# H4_MainController_Rev_1.net
KiCad netlist of a schematic drawn in EAGLE
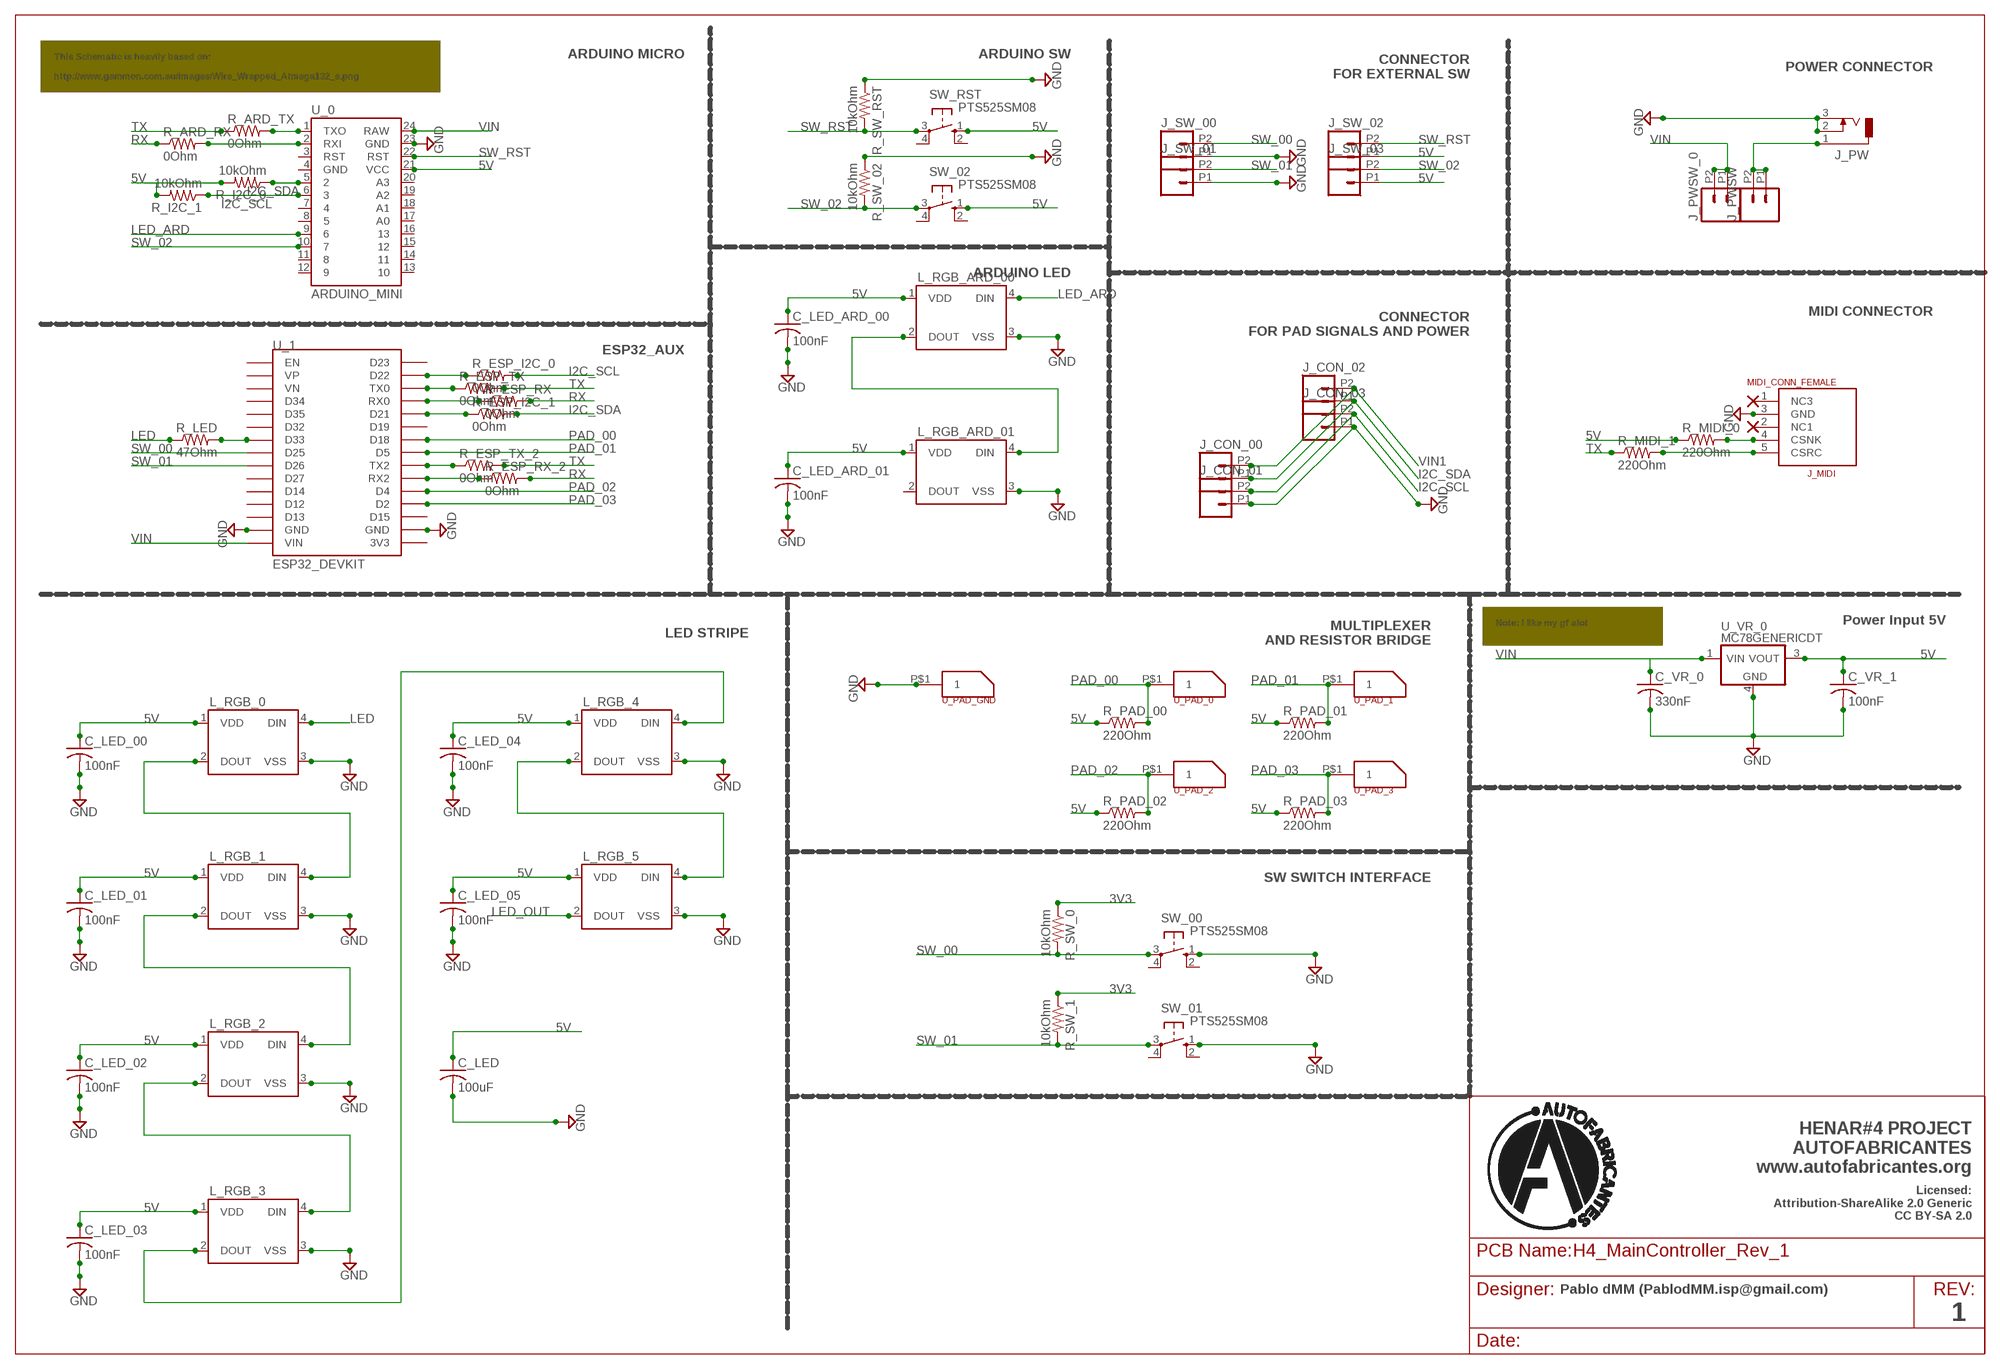
[diagram p0: schematic, sheet 1]

(export (version "E")
  (design (tool "Eeschema 10.0.6"))
  (components
    (comp (ref "C_LED")
      (value "100uF")
      (footprint "eagle-import:C1210")
      (libsource (lib "eagle-import") (part "C-USC1210"))
    )
    (comp (ref "C_LED_00")
      (value "100nF")
      (footprint "eagle-import:C0805K")
      (libsource (lib "eagle-import") (part "C-USC0805K"))
    )
    (comp (ref "C_LED_01")
      (value "100nF")
      (footprint "eagle-import:C0805K")
      (libsource (lib "eagle-import") (part "C-USC0805K"))
    )
    (comp (ref "C_LED_02")
      (value "100nF")
      (footprint "eagle-import:C0805K")
      (libsource (lib "eagle-import") (part "C-USC0805K"))
    )
    (comp (ref "C_LED_03")
      (value "100nF")
      (footprint "eagle-import:C0805K")
      (libsource (lib "eagle-import") (part "C-USC0805K"))
    )
    (comp (ref "C_LED_04")
      (value "100nF")
      (footprint "eagle-import:C0805K")
      (libsource (lib "eagle-import") (part "C-USC0805K"))
    )
    (comp (ref "C_LED_05")
      (value "100nF")
      (footprint "eagle-import:C0805K")
      (libsource (lib "eagle-import") (part "C-USC0805K"))
    )
    (comp (ref "C_LED_ARD_00")
      (value "100nF")
      (footprint "eagle-import:C0805K")
      (libsource (lib "eagle-import") (part "C-USC0805K"))
    )
    (comp (ref "C_LED_ARD_01")
      (value "100nF")
      (footprint "eagle-import:C0805K")
      (libsource (lib "eagle-import") (part "C-USC0805K"))
    )
    (comp (ref "C_VR_0")
      (value "330nF")
      (footprint "eagle-import:C0805")
      (libsource (lib "eagle-import") (part "C-USC0805"))
    )
    (comp (ref "C_VR_1")
      (value "100nF")
      (footprint "eagle-import:C0805")
      (libsource (lib "eagle-import") (part "C-USC0805"))
    )
    (comp (ref "J_CON_00")
      (value "M022.54MM_SCREWTERM")
      (footprint "eagle-import:1X02_2.54_SCREWTERM")
      (libsource (lib "eagle-import") (part "M022.54MM_SCREWTERM"))
    )
    (comp (ref "J_CON_01")
      (value "M022.54MM_SCREWTERM")
      (footprint "eagle-import:1X02_2.54_SCREWTERM")
      (libsource (lib "eagle-import") (part "M022.54MM_SCREWTERM"))
    )
    (comp (ref "J_CON_02")
      (value "M022.54MM_SCREWTERM")
      (footprint "eagle-import:1X02_2.54_SCREWTERM")
      (libsource (lib "eagle-import") (part "M022.54MM_SCREWTERM"))
    )
    (comp (ref "J_CON_03")
      (value "M022.54MM_SCREWTERM")
      (footprint "eagle-import:1X02_2.54_SCREWTERM")
      (libsource (lib "eagle-import") (part "M022.54MM_SCREWTERM"))
    )
    (comp (ref "J_MIDI")
      (value "MIDI_CONN_FEMALE")
      (footprint "eagle-import:DIN_5_FEMALE")
      (libsource (lib "eagle-import") (part "MIDI_CONN_FEMALE"))
    )
    (comp (ref "J_PW")
      (value "DCJ0303")
      (footprint "eagle-import:DCJ0303")
      (libsource (lib "eagle-import") (part "DCJ0303"))
    )
    (comp (ref "J_PWSW")
      (value "M022.54MM_SCREWTERM")
      (footprint "eagle-import:1X02_2.54_SCREWTERM")
      (libsource (lib "eagle-import") (part "M022.54MM_SCREWTERM"))
    )
    (comp (ref "J_PWSW_0")
      (value "M022.54MM_SCREWTERM")
      (footprint "eagle-import:1X02_2.54_SCREWTERM")
      (libsource (lib "eagle-import") (part "M022.54MM_SCREWTERM"))
    )
    (comp (ref "J_SW_00")
      (value "M022.54MM_SCREWTERM")
      (footprint "eagle-import:1X02_2.54_SCREWTERM")
      (libsource (lib "eagle-import") (part "M022.54MM_SCREWTERM"))
    )
    (comp (ref "J_SW_01")
      (value "M022.54MM_SCREWTERM")
      (footprint "eagle-import:1X02_2.54_SCREWTERM")
      (libsource (lib "eagle-import") (part "M022.54MM_SCREWTERM"))
    )
    (comp (ref "J_SW_02")
      (value "M022.54MM_SCREWTERM")
      (footprint "eagle-import:1X02_2.54_SCREWTERM")
      (libsource (lib "eagle-import") (part "M022.54MM_SCREWTERM"))
    )
    (comp (ref "J_SW_03")
      (value "M022.54MM_SCREWTERM")
      (footprint "eagle-import:1X02_2.54_SCREWTERM")
      (libsource (lib "eagle-import") (part "M022.54MM_SCREWTERM"))
    )
    (comp (ref "L_RGB_0")
      (value "WS2812B")
      (footprint "eagle-import:WS2812B")
      (libsource (lib "eagle-import") (part "WS2812B"))
    )
    (comp (ref "L_RGB_1")
      (value "WS2812B")
      (footprint "eagle-import:WS2812B")
      (libsource (lib "eagle-import") (part "WS2812B"))
    )
    (comp (ref "L_RGB_2")
      (value "WS2812B")
      (footprint "eagle-import:WS2812B")
      (libsource (lib "eagle-import") (part "WS2812B"))
    )
    (comp (ref "L_RGB_3")
      (value "WS2812B")
      (footprint "eagle-import:WS2812B")
      (libsource (lib "eagle-import") (part "WS2812B"))
    )
    (comp (ref "L_RGB_4")
      (value "WS2812B")
      (footprint "eagle-import:WS2812B")
      (libsource (lib "eagle-import") (part "WS2812B"))
    )
    (comp (ref "L_RGB_5")
      (value "WS2812B")
      (footprint "eagle-import:WS2812B")
      (libsource (lib "eagle-import") (part "WS2812B"))
    )
    (comp (ref "L_RGB_ARD_00")
      (value "WS2812B")
      (footprint "eagle-import:WS2812B")
      (libsource (lib "eagle-import") (part "WS2812B"))
    )
    (comp (ref "L_RGB_ARD_01")
      (value "WS2812B")
      (footprint "eagle-import:WS2812B")
      (libsource (lib "eagle-import") (part "WS2812B"))
    )
    (comp (ref "R_ARD_RX")
      (value "0Ohm")
      (footprint "eagle-import:M0805")
      (libsource (lib "eagle-import") (part "R-US_M0805"))
    )
    (comp (ref "R_ARD_TX")
      (value "0Ohm")
      (footprint "eagle-import:M0805")
      (libsource (lib "eagle-import") (part "R-US_M0805"))
    )
    (comp (ref "R_ESP_I2C_0")
      (value "0Ohm")
      (footprint "eagle-import:M0805")
      (libsource (lib "eagle-import") (part "R-US_M0805"))
    )
    (comp (ref "R_ESP_I2C_1")
      (value "0Ohm")
      (footprint "eagle-import:M0805")
      (libsource (lib "eagle-import") (part "R-US_M0805"))
    )
    (comp (ref "R_ESP_RX")
      (value "0Ohm")
      (footprint "eagle-import:M0805")
      (libsource (lib "eagle-import") (part "R-US_M0805"))
    )
    (comp (ref "R_ESP_RX_2")
      (value "0Ohm")
      (footprint "eagle-import:M0805")
      (libsource (lib "eagle-import") (part "R-US_M0805"))
    )
    (comp (ref "R_ESP_TX")
      (value "0Ohm")
      (footprint "eagle-import:M0805")
      (libsource (lib "eagle-import") (part "R-US_M0805"))
    )
    (comp (ref "R_ESP_TX_2")
      (value "0Ohm")
      (footprint "eagle-import:M0805")
      (libsource (lib "eagle-import") (part "R-US_M0805"))
    )
    (comp (ref "R_I2C_0")
      (value "10kOhm")
      (footprint "eagle-import:M0805")
      (libsource (lib "eagle-import") (part "R-US_M0805"))
    )
    (comp (ref "R_I2C_1")
      (value "10kOhm")
      (footprint "eagle-import:M0805")
      (libsource (lib "eagle-import") (part "R-US_M0805"))
    )
    (comp (ref "R_LED")
      (value "47Ohm")
      (footprint "eagle-import:M0805")
      (libsource (lib "eagle-import") (part "R-US_M0805"))
    )
    (comp (ref "R_MIDI_0")
      (value "220Ohm")
      (footprint "eagle-import:M0805")
      (libsource (lib "eagle-import") (part "R-US_M0805"))
    )
    (comp (ref "R_MIDI_1")
      (value "220Ohm")
      (footprint "eagle-import:M0805")
      (libsource (lib "eagle-import") (part "R-US_M0805"))
    )
    (comp (ref "R_PAD_00")
      (value "220Ohm")
      (footprint "eagle-import:M0805")
      (libsource (lib "eagle-import") (part "R-US_M0805"))
    )
    (comp (ref "R_PAD_01")
      (value "220Ohm")
      (footprint "eagle-import:M0805")
      (libsource (lib "eagle-import") (part "R-US_M0805"))
    )
    (comp (ref "R_PAD_02")
      (value "220Ohm")
      (footprint "eagle-import:M0805")
      (libsource (lib "eagle-import") (part "R-US_M0805"))
    )
    (comp (ref "R_PAD_03")
      (value "220Ohm")
      (footprint "eagle-import:M0805")
      (libsource (lib "eagle-import") (part "R-US_M0805"))
    )
    (comp (ref "R_SW_0")
      (value "10kOhm")
      (footprint "eagle-import:M0805")
      (libsource (lib "eagle-import") (part "R-US_M0805"))
    )
    (comp (ref "R_SW_1")
      (value "10kOhm")
      (footprint "eagle-import:M0805")
      (libsource (lib "eagle-import") (part "R-US_M0805"))
    )
    (comp (ref "R_SW_02")
      (value "10kOhm")
      (footprint "eagle-import:M0805")
      (libsource (lib "eagle-import") (part "R-US_M0805"))
    )
    (comp (ref "R_SW_RST")
      (value "10kOhm")
      (footprint "eagle-import:M0805")
      (libsource (lib "eagle-import") (part "R-US_M0805"))
    )
    (comp (ref "SW_00")
      (value "PTS525SM08")
      (footprint "eagle-import:SM08")
      (fields (field (name "MF") "C&K Components") (field (name "MPN") "PTS525SM08SMTR2LFS"))
      (libsource (lib "eagle-import") (part "PTS52508SM"))
    )
    (comp (ref "SW_01")
      (value "PTS525SM08")
      (footprint "eagle-import:SM08")
      (fields (field (name "MF") "C&K Components") (field (name "MPN") "PTS525SM08SMTR2LFS"))
      (libsource (lib "eagle-import") (part "PTS52508SM"))
    )
    (comp (ref "SW_02")
      (value "PTS525SM08")
      (footprint "eagle-import:SM08")
      (fields (field (name "MF") "C&K Components") (field (name "MPN") "PTS525SM08SMTR2LFS"))
      (libsource (lib "eagle-import") (part "PTS52508SM"))
    )
    (comp (ref "SW_RST")
      (value "PTS525SM08")
      (footprint "eagle-import:SM08")
      (fields (field (name "MF") "C&K Components") (field (name "MPN") "PTS525SM08SMTR2LFS"))
      (libsource (lib "eagle-import") (part "PTS52508SM"))
    )
    (comp (ref "U_0")
      (value "ARDUINO_MINI")
      (footprint "eagle-import:ARDUINO_MINI")
      (libsource (lib "eagle-import") (part "ARDUINO_MINI"))
    )
    (comp (ref "U_1")
      (value "ESP32_DEVKIT")
      (footprint "eagle-import:ESP32_DEVKIT")
      (libsource (lib "eagle-import") (part "ESP32_DEVKIT"))
    )
    (comp (ref "U_PAD_0")
      (value "PAD_CONNECTOR_MULTI")
      (footprint "eagle-import:PAD_CONNECTOR_MULTI")
      (libsource (lib "eagle-import") (part "PAD_CONNECTOR_MULTI"))
    )
    (comp (ref "U_PAD_1")
      (value "PAD_CONNECTOR_MULTI")
      (footprint "eagle-import:PAD_CONNECTOR_MULTI")
      (libsource (lib "eagle-import") (part "PAD_CONNECTOR_MULTI"))
    )
    (comp (ref "U_PAD_2")
      (value "PAD_CONNECTOR_MULTI")
      (footprint "eagle-import:PAD_CONNECTOR_MULTI")
      (libsource (lib "eagle-import") (part "PAD_CONNECTOR_MULTI"))
    )
    (comp (ref "U_PAD_3")
      (value "PAD_CONNECTOR_MULTI")
      (footprint "eagle-import:PAD_CONNECTOR_MULTI")
      (libsource (lib "eagle-import") (part "PAD_CONNECTOR_MULTI"))
    )
    (comp (ref "U_PAD_GND")
      (value "PAD_CONNECTOR_MULTI")
      (footprint "eagle-import:PAD_CONNECTOR_MULTI")
      (libsource (lib "eagle-import") (part "PAD_CONNECTOR_MULTI"))
    )
    (comp (ref "U_VR_0")
      (value "MC78GENERICDT")
      (footprint "eagle-import:DPAK-3")
      (libsource (lib "eagle-import") (part "MC78DTGENERIC"))
    )
  )
  (nets
    (net (code "1") (name "/3V3") (class "Default")
      (node (ref "R_SW_0") (pin "1") (pinfunction "1_1") (pintype "passive"))
      (node (ref "R_SW_1") (pin "1") (pinfunction "1_1") (pintype "passive"))
    )
    (net (code "2") (name "/5V") (class "Default")
      (node (ref "C_LED") (pin "1") (pinfunction "1_1") (pintype "passive"))
      (node (ref "C_LED_00") (pin "1") (pinfunction "1_1") (pintype "passive"))
      (node (ref "C_LED_01") (pin "1") (pinfunction "1_1") (pintype "passive"))
      (node (ref "C_LED_02") (pin "1") (pinfunction "1_1") (pintype "passive"))
      (node (ref "C_LED_03") (pin "1") (pinfunction "1_1") (pintype "passive"))
      (node (ref "C_LED_04") (pin "1") (pinfunction "1_1") (pintype "passive"))
      (node (ref "C_LED_05") (pin "1") (pinfunction "1_1") (pintype "passive"))
      (node (ref "C_LED_ARD_00") (pin "1") (pinfunction "1_1") (pintype "passive"))
      (node (ref "C_LED_ARD_01") (pin "1") (pinfunction "1_1") (pintype "passive"))
      (node (ref "C_VR_1") (pin "1") (pinfunction "1_1") (pintype "passive"))
      (node (ref "J_SW_02") (pin "P1") (pinfunction "1_P1") (pintype "passive"))
      (node (ref "J_SW_03") (pin "P1") (pinfunction "1_P1") (pintype "passive"))
      (node (ref "L_RGB_0") (pin "1") (pinfunction "VDD_1") (pintype "power_in"))
      (node (ref "L_RGB_1") (pin "1") (pinfunction "VDD_1") (pintype "power_in"))
      (node (ref "L_RGB_2") (pin "1") (pinfunction "VDD_1") (pintype "power_in"))
      (node (ref "L_RGB_3") (pin "1") (pinfunction "VDD_1") (pintype "power_in"))
      (node (ref "L_RGB_4") (pin "1") (pinfunction "VDD_1") (pintype "power_in"))
      (node (ref "L_RGB_5") (pin "1") (pinfunction "VDD_1") (pintype "power_in"))
      (node (ref "L_RGB_ARD_00") (pin "1") (pinfunction "VDD_1") (pintype "power_in"))
      (node (ref "L_RGB_ARD_01") (pin "1") (pinfunction "VDD_1") (pintype "power_in"))
      (node (ref "R_I2C_0") (pin "2") (pinfunction "2_2") (pintype "passive"))
      (node (ref "R_I2C_1") (pin "2") (pinfunction "2_2") (pintype "passive"))
      (node (ref "R_MIDI_0") (pin "1") (pinfunction "1_1") (pintype "passive"))
      (node (ref "R_PAD_00") (pin "1") (pinfunction "1_1") (pintype "passive"))
      (node (ref "R_PAD_01") (pin "1") (pinfunction "1_1") (pintype "passive"))
      (node (ref "R_PAD_02") (pin "1") (pinfunction "1_1") (pintype "passive"))
      (node (ref "R_PAD_03") (pin "1") (pinfunction "1_1") (pintype "passive"))
      (node (ref "SW_02") (pin "1") (pinfunction "S_1") (pintype "passive"))
      (node (ref "SW_RST") (pin "1") (pinfunction "S_1") (pintype "passive"))
      (node (ref "U_0") (pin "21") (pinfunction "VCC_21") (pintype "bidirectional"))
      (node (ref "U_VR_0") (pin "3") (pinfunction "VOUT_3") (pintype "power_in"))
    )
    (net (code "3") (name "/I2C_SCL") (class "Default")
      (node (ref "J_CON_01") (pin "P2") (pinfunction "2_P2") (pintype "passive"))
      (node (ref "J_CON_03") (pin "P2") (pinfunction "2_P2") (pintype "passive"))
      (node (ref "R_ESP_I2C_0") (pin "2") (pinfunction "2_2") (pintype "passive"))
      (node (ref "R_I2C_1") (pin "1") (pinfunction "1_1") (pintype "passive"))
      (node (ref "U_0") (pin "6") (pinfunction "3_6") (pintype "bidirectional"))
    )
    (net (code "4") (name "/I2C_SDA") (class "Default")
      (node (ref "J_CON_00") (pin "P1") (pinfunction "1_P1") (pintype "passive"))
      (node (ref "J_CON_02") (pin "P1") (pinfunction "1_P1") (pintype "passive"))
      (node (ref "R_ESP_I2C_1") (pin "2") (pinfunction "2_2") (pintype "passive"))
      (node (ref "R_I2C_0") (pin "1") (pinfunction "1_1") (pintype "passive"))
      (node (ref "U_0") (pin "5") (pinfunction "2_5") (pintype "bidirectional"))
    )
    (net (code "5") (name "/LED") (class "Default")
      (node (ref "L_RGB_0") (pin "4") (pinfunction "DIN_4") (pintype "input"))
      (node (ref "R_LED") (pin "1") (pinfunction "1_1") (pintype "passive"))
    )
    (net (code "6") (name "/LED_ARD") (class "Default")
      (node (ref "L_RGB_ARD_00") (pin "4") (pinfunction "DIN_4") (pintype "input"))
      (node (ref "U_0") (pin "9") (pinfunction "6_9") (pintype "bidirectional"))
    )
    (net (code "7") (name "/LED_OUT") (class "Default")
      (node (ref "L_RGB_5") (pin "2") (pinfunction "DOUT_2") (pintype "output"))
    )
    (net (code "8") (name "/PAD_00") (class "Default")
      (node (ref "R_PAD_00") (pin "2") (pinfunction "2_2") (pintype "passive"))
      (node (ref "U_1") (pin "D18") (pinfunction "D18_D18") (pintype "bidirectional"))
      (node (ref "U_PAD_0") (pin "P$1") (pinfunction "1_P$1") (pintype "bidirectional"))
    )
    (net (code "9") (name "/PAD_01") (class "Default")
      (node (ref "R_PAD_01") (pin "2") (pinfunction "2_2") (pintype "passive"))
      (node (ref "U_1") (pin "D5") (pinfunction "D5_D5") (pintype "bidirectional"))
      (node (ref "U_PAD_1") (pin "P$1") (pinfunction "1_P$1") (pintype "bidirectional"))
    )
    (net (code "10") (name "/PAD_02") (class "Default")
      (node (ref "R_PAD_02") (pin "2") (pinfunction "2_2") (pintype "passive"))
      (node (ref "U_1") (pin "D4") (pinfunction "D4_D4") (pintype "bidirectional"))
      (node (ref "U_PAD_2") (pin "P$1") (pinfunction "1_P$1") (pintype "bidirectional"))
    )
    (net (code "11") (name "/PAD_03") (class "Default")
      (node (ref "R_PAD_03") (pin "2") (pinfunction "2_2") (pintype "passive"))
      (node (ref "U_1") (pin "D2") (pinfunction "D2_D2") (pintype "bidirectional"))
      (node (ref "U_PAD_3") (pin "P$1") (pinfunction "1_P$1") (pintype "bidirectional"))
    )
    (net (code "12") (name "/RX") (class "Default")
      (node (ref "R_ARD_RX") (pin "1") (pinfunction "1_1") (pintype "passive"))
      (node (ref "R_ESP_RX") (pin "2") (pinfunction "2_2") (pintype "passive"))
      (node (ref "R_ESP_RX_2") (pin "2") (pinfunction "2_2") (pintype "passive"))
    )
    (net (code "13") (name "/SW_00") (class "Default")
      (node (ref "J_SW_00") (pin "P2") (pinfunction "2_P2") (pintype "passive"))
      (node (ref "R_SW_0") (pin "2") (pinfunction "2_2") (pintype "passive"))
      (node (ref "SW_00") (pin "3") (pinfunction "P_3") (pintype "passive"))
      (node (ref "U_1") (pin "D25") (pinfunction "D25_D25") (pintype "bidirectional"))
    )
    (net (code "14") (name "/SW_01") (class "Default")
      (node (ref "J_SW_01") (pin "P2") (pinfunction "2_P2") (pintype "passive"))
      (node (ref "R_SW_1") (pin "2") (pinfunction "2_2") (pintype "passive"))
      (node (ref "SW_01") (pin "3") (pinfunction "P_3") (pintype "passive"))
      (node (ref "U_1") (pin "D26") (pinfunction "D26_D26") (pintype "bidirectional"))
    )
    (net (code "15") (name "/SW_02") (class "Default")
      (node (ref "J_SW_03") (pin "P2") (pinfunction "2_P2") (pintype "passive"))
      (node (ref "R_SW_02") (pin "2") (pinfunction "2_2") (pintype "passive"))
      (node (ref "SW_02") (pin "3") (pinfunction "P_3") (pintype "passive"))
      (node (ref "U_0") (pin "10") (pinfunction "7_10") (pintype "bidirectional"))
    )
    (net (code "16") (name "/SW_RST") (class "Default")
      (node (ref "J_SW_02") (pin "P2") (pinfunction "2_P2") (pintype "passive"))
      (node (ref "R_SW_RST") (pin "2") (pinfunction "2_2") (pintype "passive"))
      (node (ref "SW_RST") (pin "3") (pinfunction "P_3") (pintype "passive"))
      (node (ref "U_0") (pin "22") (pinfunction "RST_22") (pintype "bidirectional"))
    )
    (net (code "17") (name "/TX") (class "Default")
      (node (ref "R_ARD_TX") (pin "1") (pinfunction "1_1") (pintype "passive"))
      (node (ref "R_ESP_TX") (pin "2") (pinfunction "2_2") (pintype "passive"))
      (node (ref "R_ESP_TX_2") (pin "2") (pinfunction "2_2") (pintype "passive"))
      (node (ref "R_MIDI_1") (pin "1") (pinfunction "1_1") (pintype "passive"))
    )
    (net (code "18") (name "/VIN") (class "Default")
      (node (ref "C_VR_0") (pin "1") (pinfunction "1_1") (pintype "passive"))
      (node (ref "J_PWSW_0") (pin "P1") (pinfunction "1_P1") (pintype "passive"))
      (node (ref "J_PWSW_0") (pin "P2") (pinfunction "2_P2") (pintype "passive"))
      (node (ref "U_0") (pin "24") (pinfunction "RAW_24") (pintype "bidirectional"))
      (node (ref "U_1") (pin "VIN") (pinfunction "VIN_VIN") (pintype "bidirectional"))
      (node (ref "U_VR_0") (pin "1") (pinfunction "VIN_1") (pintype "power_in"))
    )
    (net (code "19") (name "/VIN1") (class "Default")
      (node (ref "J_CON_00") (pin "P2") (pinfunction "2_P2") (pintype "passive"))
      (node (ref "J_CON_02") (pin "P2") (pinfunction "2_P2") (pintype "passive"))
    )
    (net (code "20") (name "GND") (class "Default")
      (node (ref "C_LED") (pin "2") (pinfunction "2_2") (pintype "passive"))
      (node (ref "C_LED_00") (pin "2") (pinfunction "2_2") (pintype "passive"))
      (node (ref "C_LED_01") (pin "2") (pinfunction "2_2") (pintype "passive"))
      (node (ref "C_LED_02") (pin "2") (pinfunction "2_2") (pintype "passive"))
      (node (ref "C_LED_03") (pin "2") (pinfunction "2_2") (pintype "passive"))
      (node (ref "C_LED_04") (pin "2") (pinfunction "2_2") (pintype "passive"))
      (node (ref "C_LED_05") (pin "2") (pinfunction "2_2") (pintype "passive"))
      (node (ref "C_LED_ARD_00") (pin "2") (pinfunction "2_2") (pintype "passive"))
      (node (ref "C_LED_ARD_01") (pin "2") (pinfunction "2_2") (pintype "passive"))
      (node (ref "C_VR_0") (pin "2") (pinfunction "2_2") (pintype "passive"))
      (node (ref "C_VR_1") (pin "2") (pinfunction "2_2") (pintype "passive"))
      (node (ref "J_CON_01") (pin "P1") (pinfunction "1_P1") (pintype "passive"))
      (node (ref "J_CON_03") (pin "P1") (pinfunction "1_P1") (pintype "passive"))
      (node (ref "J_MIDI") (pin "3") (pinfunction "GND_3") (pintype "bidirectional"))
      (node (ref "J_PW") (pin "2") (pinfunction "2_2") (pintype "passive"))
      (node (ref "J_PW") (pin "3") (pinfunction "3_3") (pintype "passive"))
      (node (ref "J_SW_00") (pin "P1") (pinfunction "1_P1") (pintype "passive"))
      (node (ref "J_SW_01") (pin "P1") (pinfunction "1_P1") (pintype "passive"))
      (node (ref "L_RGB_0") (pin "3") (pinfunction "VSS_3") (pintype "power_in"))
      (node (ref "L_RGB_1") (pin "3") (pinfunction "VSS_3") (pintype "power_in"))
      (node (ref "L_RGB_2") (pin "3") (pinfunction "VSS_3") (pintype "power_in"))
      (node (ref "L_RGB_3") (pin "3") (pinfunction "VSS_3") (pintype "power_in"))
      (node (ref "L_RGB_4") (pin "3") (pinfunction "VSS_3") (pintype "power_in"))
      (node (ref "L_RGB_5") (pin "3") (pinfunction "VSS_3") (pintype "power_in"))
      (node (ref "L_RGB_ARD_00") (pin "3") (pinfunction "VSS_3") (pintype "power_in"))
      (node (ref "L_RGB_ARD_01") (pin "3") (pinfunction "VSS_3") (pintype "power_in"))
      (node (ref "R_SW_02") (pin "1") (pinfunction "1_1") (pintype "passive"))
      (node (ref "R_SW_RST") (pin "1") (pinfunction "1_1") (pintype "passive"))
      (node (ref "SW_00") (pin "1") (pinfunction "S_1") (pintype "passive"))
      (node (ref "SW_01") (pin "1") (pinfunction "S_1") (pintype "passive"))
      (node (ref "U_0") (pin "23") (pinfunction "GND_23") (pintype "bidirectional"))
      (node (ref "U_1") (pin "GND@1") (pinfunction "GND_GND@1") (pintype "bidirectional"))
      (node (ref "U_1") (pin "GND@2") (pinfunction "GND_GND@2") (pintype "bidirectional"))
      (node (ref "U_PAD_GND") (pin "P$1") (pinfunction "1_P$1") (pintype "bidirectional"))
      (node (ref "U_VR_0") (pin "4") (pinfunction "GND_4") (pintype "power_in"))
    )
    (net (code "21") (name "Net-(J_MIDI-CSNK)") (class "Default")
      (node (ref "J_MIDI") (pin "4") (pinfunction "CSNK_4") (pintype "bidirectional"))
      (node (ref "R_MIDI_0") (pin "2") (pinfunction "2_2") (pintype "passive"))
    )
    (net (code "22") (name "Net-(J_MIDI-CSRC)") (class "Default")
      (node (ref "J_MIDI") (pin "5") (pinfunction "CSRC_5") (pintype "bidirectional"))
      (node (ref "R_MIDI_1") (pin "2") (pinfunction "2_2") (pintype "passive"))
    )
    (net (code "23") (name "Net-(J_PWSW-1)") (class "Default")
      (node (ref "J_PW") (pin "1") (pinfunction "1_1") (pintype "passive"))
      (node (ref "J_PWSW") (pin "P1") (pinfunction "1_P1") (pintype "passive"))
      (node (ref "J_PWSW") (pin "P2") (pinfunction "2_P2") (pintype "passive"))
    )
    (net (code "24") (name "Net-(L_RGB_0-DOUT)") (class "Default")
      (node (ref "L_RGB_0") (pin "2") (pinfunction "DOUT_2") (pintype "output"))
      (node (ref "L_RGB_1") (pin "4") (pinfunction "DIN_4") (pintype "input"))
    )
    (net (code "25") (name "Net-(L_RGB_1-DOUT)") (class "Default")
      (node (ref "L_RGB_1") (pin "2") (pinfunction "DOUT_2") (pintype "output"))
      (node (ref "L_RGB_2") (pin "4") (pinfunction "DIN_4") (pintype "input"))
    )
    (net (code "26") (name "Net-(L_RGB_2-DOUT)") (class "Default")
      (node (ref "L_RGB_2") (pin "2") (pinfunction "DOUT_2") (pintype "output"))
      (node (ref "L_RGB_3") (pin "4") (pinfunction "DIN_4") (pintype "input"))
    )
    (net (code "27") (name "Net-(L_RGB_3-DOUT)") (class "Default")
      (node (ref "L_RGB_3") (pin "2") (pinfunction "DOUT_2") (pintype "output"))
      (node (ref "L_RGB_4") (pin "4") (pinfunction "DIN_4") (pintype "input"))
    )
    (net (code "28") (name "Net-(L_RGB_4-DOUT)") (class "Default")
      (node (ref "L_RGB_4") (pin "2") (pinfunction "DOUT_2") (pintype "output"))
      (node (ref "L_RGB_5") (pin "4") (pinfunction "DIN_4") (pintype "input"))
    )
    (net (code "29") (name "Net-(L_RGB_ARD_00-DOUT)") (class "Default")
      (node (ref "L_RGB_ARD_00") (pin "2") (pinfunction "DOUT_2") (pintype "output"))
      (node (ref "L_RGB_ARD_01") (pin "4") (pinfunction "DIN_4") (pintype "input"))
    )
    (net (code "30") (name "Net-(R_ESP_I2C_0-Pad1)") (class "Default")
      (node (ref "R_ESP_I2C_0") (pin "1") (pinfunction "1_1") (pintype "passive"))
      (node (ref "U_1") (pin "D22") (pinfunction "D22_D22") (pintype "bidirectional"))
    )
    (net (code "31") (name "Net-(R_ESP_I2C_1-Pad1)") (class "Default")
      (node (ref "R_ESP_I2C_1") (pin "1") (pinfunction "1_1") (pintype "passive"))
      (node (ref "U_1") (pin "D21") (pinfunction "D21_D21") (pintype "bidirectional"))
    )
    (net (code "32") (name "Net-(R_ESP_RX-Pad1)") (class "Default")
      (node (ref "R_ESP_RX") (pin "1") (pinfunction "1_1") (pintype "passive"))
      (node (ref "U_1") (pin "RX0") (pinfunction "RX0_RX0") (pintype "bidirectional"))
    )
    (net (code "33") (name "Net-(R_ESP_RX_2-Pad1)") (class "Default")
      (node (ref "R_ESP_RX_2") (pin "1") (pinfunction "1_1") (pintype "passive"))
      (node (ref "U_1") (pin "RX2") (pinfunction "RX2_RX2") (pintype "bidirectional"))
    )
    (net (code "34") (name "Net-(R_ESP_TX-Pad1)") (class "Default")
      (node (ref "R_ESP_TX") (pin "1") (pinfunction "1_1") (pintype "passive"))
      (node (ref "U_1") (pin "TX0") (pinfunction "TX0_TX0") (pintype "bidirectional"))
    )
    (net (code "35") (name "Net-(R_ESP_TX_2-Pad1)") (class "Default")
      (node (ref "R_ESP_TX_2") (pin "1") (pinfunction "1_1") (pintype "passive"))
      (node (ref "U_1") (pin "TX2") (pinfunction "TX2_TX2") (pintype "bidirectional"))
    )
    (net (code "36") (name "Net-(R_LED-Pad2)") (class "Default")
      (node (ref "R_LED") (pin "2") (pinfunction "2_2") (pintype "passive"))
      (node (ref "U_1") (pin "D33") (pinfunction "D33_D33") (pintype "bidirectional"))
    )
    (net (code "37") (name "Net-(U_0-RXI)") (class "Default")
      (node (ref "R_ARD_RX") (pin "2") (pinfunction "2_2") (pintype "passive"))
      (node (ref "U_0") (pin "2") (pinfunction "RXI_2") (pintype "bidirectional"))
    )
    (net (code "38") (name "Net-(U_0-TXO)") (class "Default")
      (node (ref "R_ARD_TX") (pin "2") (pinfunction "2_2") (pintype "passive"))
      (node (ref "U_0") (pin "1") (pinfunction "TXO_1") (pintype "bidirectional"))
    )
    (net (code "39") (name "unconnected-(J_MIDI-NC1-Pad2)") (class "Default")
      (node (ref "J_MIDI") (pin "2") (pinfunction "NC1_2") (pintype "bidirectional"))
    )
    (net (code "40") (name "unconnected-(J_MIDI-NC3-Pad1)") (class "Default")
      (node (ref "J_MIDI") (pin "1") (pinfunction "NC3_1") (pintype "bidirectional"))
    )
    (net (code "41") (name "unconnected-(L_RGB_ARD_01-DOUT-Pad2)") (class "Default")
      (node (ref "L_RGB_ARD_01") (pin "2") (pinfunction "DOUT_2") (pintype "output"))
    )
    (net (code "42") (name "unconnected-(SW_00-P-Pad4)") (class "Default")
      (node (ref "SW_00") (pin "4") (pinfunction "P_4") (pintype "passive"))
    )
    (net (code "43") (name "unconnected-(SW_00-S-Pad2)") (class "Default")
      (node (ref "SW_00") (pin "2") (pinfunction "S_2") (pintype "passive"))
    )
    (net (code "44") (name "unconnected-(SW_01-P-Pad4)") (class "Default")
      (node (ref "SW_01") (pin "4") (pinfunction "P_4") (pintype "passive"))
    )
    (net (code "45") (name "unconnected-(SW_01-S-Pad2)") (class "Default")
      (node (ref "SW_01") (pin "2") (pinfunction "S_2") (pintype "passive"))
    )
    (net (code "46") (name "unconnected-(SW_02-P-Pad4)") (class "Default")
      (node (ref "SW_02") (pin "4") (pinfunction "P_4") (pintype "passive"))
    )
    (net (code "47") (name "unconnected-(SW_02-S-Pad2)") (class "Default")
      (node (ref "SW_02") (pin "2") (pinfunction "S_2") (pintype "passive"))
    )
    (net (code "48") (name "unconnected-(SW_RST-P-Pad4)") (class "Default")
      (node (ref "SW_RST") (pin "4") (pinfunction "P_4") (pintype "passive"))
    )
    (net (code "49") (name "unconnected-(SW_RST-S-Pad2)") (class "Default")
      (node (ref "SW_RST") (pin "2") (pinfunction "S_2") (pintype "passive"))
    )
    (net (code "50") (name "unconnected-(U_0-4-Pad7)") (class "Default")
      (node (ref "U_0") (pin "7") (pinfunction "4_7") (pintype "bidirectional"))
    )
    (net (code "51") (name "unconnected-(U_0-5-Pad8)") (class "Default")
      (node (ref "U_0") (pin "8") (pinfunction "5_8") (pintype "bidirectional"))
    )
    (net (code "52") (name "unconnected-(U_0-8-Pad11)") (class "Default")
      (node (ref "U_0") (pin "11") (pinfunction "8_11") (pintype "bidirectional"))
    )
    (net (code "53") (name "unconnected-(U_0-9-Pad12)") (class "Default")
      (node (ref "U_0") (pin "12") (pinfunction "9_12") (pintype "bidirectional"))
    )
    (net (code "54") (name "unconnected-(U_0-10-Pad13)") (class "Default")
      (node (ref "U_0") (pin "13") (pinfunction "10_13") (pintype "bidirectional"))
    )
    (net (code "55") (name "unconnected-(U_0-11-Pad14)") (class "Default")
      (node (ref "U_0") (pin "14") (pinfunction "11_14") (pintype "bidirectional"))
    )
    (net (code "56") (name "unconnected-(U_0-12-Pad15)") (class "Default")
      (node (ref "U_0") (pin "15") (pinfunction "12_15") (pintype "bidirectional"))
    )
    (net (code "57") (name "unconnected-(U_0-13-Pad16)") (class "Default")
      (node (ref "U_0") (pin "16") (pinfunction "13_16") (pintype "bidirectional"))
    )
    (net (code "58") (name "unconnected-(U_0-A0-Pad17)") (class "Default")
      (node (ref "U_0") (pin "17") (pinfunction "A0_17") (pintype "bidirectional"))
    )
    (net (code "59") (name "unconnected-(U_0-A1-Pad18)") (class "Default")
      (node (ref "U_0") (pin "18") (pinfunction "A1_18") (pintype "bidirectional"))
    )
    (net (code "60") (name "unconnected-(U_0-A2-Pad19)") (class "Default")
      (node (ref "U_0") (pin "19") (pinfunction "A2_19") (pintype "bidirectional"))
    )
    (net (code "61") (name "unconnected-(U_0-A3-Pad20)") (class "Default")
      (node (ref "U_0") (pin "20") (pinfunction "A3_20") (pintype "bidirectional"))
    )
    (net (code "62") (name "unconnected-(U_0-GND-Pad4)") (class "Default")
      (node (ref "U_0") (pin "4") (pinfunction "GND_4") (pintype "bidirectional"))
    )
    (net (code "63") (name "unconnected-(U_0-RST-Pad3)") (class "Default")
      (node (ref "U_0") (pin "3") (pinfunction "RST_3") (pintype "bidirectional"))
    )
    (net (code "64") (name "unconnected-(U_1-Pad3V3)") (class "Default")
      (node (ref "U_1") (pin "3V3") (pinfunction "3V3_3V3") (pintype "bidirectional"))
    )
    (net (code "65") (name "unconnected-(U_1-PadD12)") (class "Default")
      (node (ref "U_1") (pin "D12") (pinfunction "D12_D12") (pintype "bidirectional"))
    )
    (net (code "66") (name "unconnected-(U_1-PadD13)") (class "Default")
      (node (ref "U_1") (pin "D13") (pinfunction "D13_D13") (pintype "bidirectional"))
    )
    (net (code "67") (name "unconnected-(U_1-PadD14)") (class "Default")
      (node (ref "U_1") (pin "D14") (pinfunction "D14_D14") (pintype "bidirectional"))
    )
    (net (code "68") (name "unconnected-(U_1-PadD15)") (class "Default")
      (node (ref "U_1") (pin "D15") (pinfunction "D15_D15") (pintype "bidirectional"))
    )
    (net (code "69") (name "unconnected-(U_1-PadD19)") (class "Default")
      (node (ref "U_1") (pin "D19") (pinfunction "D19_D19") (pintype "bidirectional"))
    )
    (net (code "70") (name "unconnected-(U_1-PadD23)") (class "Default")
      (node (ref "U_1") (pin "D23") (pinfunction "D23_D23") (pintype "bidirectional"))
    )
    (net (code "71") (name "unconnected-(U_1-PadD27)") (class "Default")
      (node (ref "U_1") (pin "D27") (pinfunction "D27_D27") (pintype "bidirectional"))
    )
    (net (code "72") (name "unconnected-(U_1-PadD32)") (class "Default")
      (node (ref "U_1") (pin "D32") (pinfunction "D32_D32") (pintype "bidirectional"))
    )
    (net (code "73") (name "unconnected-(U_1-PadD34)") (class "Default")
      (node (ref "U_1") (pin "D34") (pinfunction "D34_D34") (pintype "bidirectional"))
    )
    (net (code "74") (name "unconnected-(U_1-PadD35)") (class "Default")
      (node (ref "U_1") (pin "D35") (pinfunction "D35_D35") (pintype "bidirectional"))
    )
    (net (code "75") (name "unconnected-(U_1-PadEN)") (class "Default")
      (node (ref "U_1") (pin "EN") (pinfunction "EN_EN") (pintype "bidirectional"))
    )
    (net (code "76") (name "unconnected-(U_1-PadVN)") (class "Default")
      (node (ref "U_1") (pin "VN") (pinfunction "VN_VN") (pintype "bidirectional"))
    )
    (net (code "77") (name "unconnected-(U_1-PadVP)") (class "Default")
      (node (ref "U_1") (pin "VP") (pinfunction "VP_VP") (pintype "bidirectional"))
    )
  )
)
